# wisp-6-mcu.net
KiCad netlist of a schematic drawn in Altium Designer
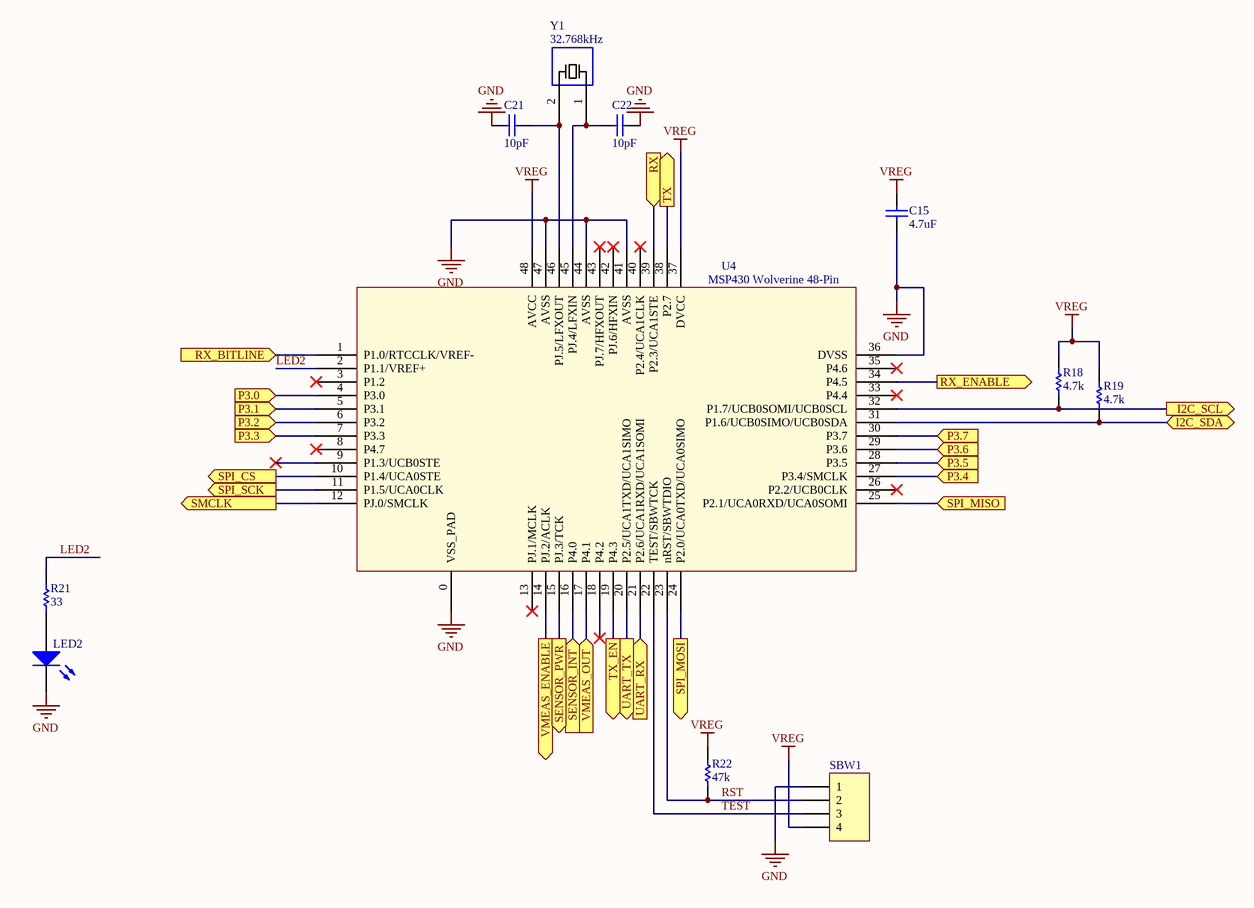
[diagram p0: wisp-6-mcu.SchDoc]

(export (version "E")
  (design (tool "Eeschema 10.0.6"))
  (components
    (comp (ref "C15")
      (value "4.7uF")
      (footprint "0402")
      (description "Ceramic Capacitor (Surface Mount)")
      (fields (field (name "MANUFACTURER") "Generic Ceramic Chip Cap (TBD)") (field (name "Comment") "Cap"))
      (libsource (lib "WISP_AD10") (part "Cap"))
    )
    (comp (ref "C21")
      (value "10pF")
      (footprint "0402")
      (description "Ceramic Capacitor (Surface Mount)")
      (fields (field (name "MANUFACTURER") "Generic Ceramic Chip Cap (TBD)") (field (name "Comment") "Cap"))
      (libsource (lib "WISP_AD10") (part "Cap"))
    )
    (comp (ref "C22")
      (value "10pF")
      (footprint "0402")
      (description "Ceramic Capacitor (Surface Mount)")
      (fields (field (name "MANUFACTURER") "Generic Ceramic Chip Cap (TBD)") (field (name "Comment") "Cap"))
      (libsource (lib "WISP_AD10") (part "Cap"))
    )
    (comp (ref "LED2")
      (value "LED")
      (footprint "Diode - 0603")
      (description "Typical RED, GREEN, YELLOW, AMBER GaAs LED")
      (libsource (lib "WISP_AD10") (part "Diode - LED"))
    )
    (comp (ref "R18")
      (value "4.7k")
      (footprint "0402")
      (description "Chip Resistor (Surface Mount)")
      (fields (field (name "MANUFACTURER") "Generic Chip Res (TBD)") (field (name "Comment") "Res"))
      (libsource (lib "WISP_AD10") (part "Res"))
    )
    (comp (ref "R19")
      (value "4.7k")
      (footprint "0402")
      (description "Chip Resistor (Surface Mount)")
      (fields (field (name "MANUFACTURER") "Generic Chip Res (TBD)") (field (name "Comment") "Res"))
      (libsource (lib "WISP_AD10") (part "Res"))
    )
    (comp (ref "R21")
      (value "33")
      (footprint "0402")
      (description "Chip Resistor (Surface Mount)")
      (fields (field (name "MANUFACTURER") "Generic Chip Res (TBD)") (field (name "Comment") "Res"))
      (libsource (lib "WISP_AD10") (part "Res"))
    )
    (comp (ref "R22")
      (value "47k")
      (footprint "0402")
      (description "Chip Resistor (Surface Mount)")
      (fields (field (name "MANUFACTURER") "Generic Chip Res (TBD)") (field (name "Comment") "Res"))
      (libsource (lib "WISP_AD10") (part "Res"))
    )
    (comp (ref "SBW1")
      (value "MHDR1X4")
      (footprint "MHDR1X4")
      (description "Header, 4-Pin")
      (fields (field (name "PUBLISHER") "Altium Limited"))
      (libsource (lib "Miscellaneous Connectors") (part "MHDR1X4"))
    )
    (comp (ref "U4")
      (value "MSP430 Wolverine 48-Pin")
      (footprint "MSP_QFN48_RGZ_PAD0")
      (description "16-bit FRAM MCU")
      (fields (field (name "PARTNUMBER") "MSP430FR5969"))
      (libsource (lib "WISP_AD10") (part "MSP430FR596X_586X_RGZ"))
    )
    (comp (ref "Y1")
      (value "32.768kHz")
      (footprint "XTAL [3.20mm x 1.50mm]")
      (description "Crystal Oscillator - [3.20mm x 1.50mm]")
      (fields
        (field (name "DIGI-KEY PART NUMBER") "example: SE2413CT-ND")
        (field (name "MANUFACTURER") "Epson Toyocom Corporation")
      )
      (libsource (lib "WISP_AD10") (part "XTAL 2-pins"))
    )
  )
  (nets
    (net (code "1") (name "/I2C_SCL") (class "Default")
      (node (ref "R18") (pin "1") (pinfunction "1_1") (pintype "passive"))
      (node (ref "U4") (pin "32") (pinfunction "P1.7/UCB0SOMI/UCB0SCL_32") (pintype "passive"))
    )
    (net (code "2") (name "/I2C_SDA") (class "Default")
      (node (ref "R19") (pin "1") (pinfunction "1_1") (pintype "passive"))
      (node (ref "U4") (pin "31") (pinfunction "P1.6/UCB0SIMO/UCB0SDA_31") (pintype "passive"))
    )
    (net (code "3") (name "/LED2") (class "Default")
      (node (ref "R21") (pin "2") (pinfunction "2_2") (pintype "passive"))
      (node (ref "U4") (pin "2") (pinfunction "P1.1/VREF+_2") (pintype "passive"))
    )
    (net (code "4") (name "/P3.0") (class "Default")
      (node (ref "U4") (pin "4") (pinfunction "P3.0_4") (pintype "passive"))
    )
    (net (code "5") (name "/P3.1") (class "Default")
      (node (ref "U4") (pin "5") (pinfunction "P3.1_5") (pintype "passive"))
    )
    (net (code "6") (name "/P3.2") (class "Default")
      (node (ref "U4") (pin "6") (pinfunction "P3.2_6") (pintype "passive"))
    )
    (net (code "7") (name "/P3.3") (class "Default")
      (node (ref "U4") (pin "7") (pinfunction "P3.3_7") (pintype "passive"))
    )
    (net (code "8") (name "/P3.4") (class "Default")
      (node (ref "U4") (pin "27") (pinfunction "P3.4/SMCLK_27") (pintype "passive"))
    )
    (net (code "9") (name "/P3.5") (class "Default")
      (node (ref "U4") (pin "28") (pinfunction "P3.5_28") (pintype "passive"))
    )
    (net (code "10") (name "/P3.6") (class "Default")
      (node (ref "U4") (pin "29") (pinfunction "P3.6_29") (pintype "passive"))
    )
    (net (code "11") (name "/P3.7") (class "Default")
      (node (ref "U4") (pin "30") (pinfunction "P3.7_30") (pintype "passive"))
    )
    (net (code "12") (name "/RST") (class "Default")
      (node (ref "R22") (pin "1") (pinfunction "1_1") (pintype "passive"))
      (node (ref "SBW1") (pin "2") (pinfunction "2_2") (pintype "passive"))
      (node (ref "U4") (pin "23") (pinfunction "nRST/SBWTDIO_23") (pintype "passive"))
    )
    (net (code "13") (name "/RX") (class "Default")
      (node (ref "U4") (pin "39") (pinfunction "P2.3/UCA1STE_39") (pintype "passive"))
    )
    (net (code "14") (name "/RX_BITLINE") (class "Default")
      (node (ref "U4") (pin "1") (pinfunction "P1.0/RTCCLK/VREF-_1") (pintype "passive"))
    )
    (net (code "15") (name "/RX_ENABLE") (class "Default")
      (node (ref "U4") (pin "34") (pinfunction "P4.5_34") (pintype "passive"))
    )
    (net (code "16") (name "/SENSOR_INT") (class "Default")
      (node (ref "U4") (pin "16") (pinfunction "P4.0_16") (pintype "passive"))
    )
    (net (code "17") (name "/SENSOR_PWR") (class "Default")
      (node (ref "U4") (pin "15") (pinfunction "PJ.3/TCK_15") (pintype "passive"))
    )
    (net (code "18") (name "/SMCLK") (class "Default")
      (node (ref "U4") (pin "12") (pinfunction "PJ.0/SMCLK_12") (pintype "passive"))
    )
    (net (code "19") (name "/SPI_CS") (class "Default")
      (node (ref "U4") (pin "10") (pinfunction "P1.4/UCA0STE_10") (pintype "passive"))
    )
    (net (code "20") (name "/SPI_MISO") (class "Default")
      (node (ref "U4") (pin "25") (pinfunction "P2.1/UCA0RXD/UCA0SOMI_25") (pintype "passive"))
    )
    (net (code "21") (name "/SPI_MOSI") (class "Default")
      (node (ref "U4") (pin "24") (pinfunction "P2.0/UCA0TXD/UCA0SIMO_24") (pintype "passive"))
    )
    (net (code "22") (name "/SPI_SCK") (class "Default")
      (node (ref "U4") (pin "11") (pinfunction "P1.5/UCA0CLK_11") (pintype "passive"))
    )
    (net (code "23") (name "/TEST") (class "Default")
      (node (ref "SBW1") (pin "3") (pinfunction "3_3") (pintype "passive"))
      (node (ref "U4") (pin "22") (pinfunction "TEST/SBWTCK_22") (pintype "passive"))
    )
    (net (code "24") (name "/TX") (class "Default")
      (node (ref "U4") (pin "38") (pinfunction "P2.7_38") (pintype "passive"))
    )
    (net (code "25") (name "/TX_EN") (class "Default")
      (node (ref "U4") (pin "19") (pinfunction "P4.3_19") (pintype "passive"))
    )
    (net (code "26") (name "/UART_RX") (class "Default")
      (node (ref "U4") (pin "21") (pinfunction "P2.6/UCA1RXD/UCA1SOMI_21") (pintype "passive"))
    )
    (net (code "27") (name "/UART_TX") (class "Default")
      (node (ref "U4") (pin "20") (pinfunction "P2.5/UCA1TXD/UCA1SIMO_20") (pintype "passive"))
    )
    (net (code "28") (name "/VMEAS_ENABLE") (class "Default")
      (node (ref "U4") (pin "14") (pinfunction "PJ.2/ACLK_14") (pintype "passive"))
    )
    (net (code "29") (name "/VMEAS_OUT") (class "Default")
      (node (ref "U4") (pin "17") (pinfunction "P4.1_17") (pintype "passive"))
    )
    (net (code "30") (name "GND") (class "Default")
      (node (ref "C15") (pin "1") (pinfunction "1_1") (pintype "passive"))
      (node (ref "C21") (pin "1") (pinfunction "1_1") (pintype "passive"))
      (node (ref "C22") (pin "1") (pinfunction "1_1") (pintype "passive"))
      (node (ref "LED2") (pin "2") (pinfunction "K_2") (pintype "passive"))
      (node (ref "SBW1") (pin "1") (pinfunction "1_1") (pintype "passive"))
      (node (ref "U4") (pin "0") (pinfunction "VSS_PAD_0") (pintype "passive"))
      (node (ref "U4") (pin "36") (pinfunction "DVSS_36") (pintype "passive"))
      (node (ref "U4") (pin "41") (pinfunction "AVSS_41") (pintype "passive"))
      (node (ref "U4") (pin "44") (pinfunction "AVSS_44") (pintype "passive"))
      (node (ref "U4") (pin "47") (pinfunction "AVSS_47") (pintype "passive"))
    )
    (net (code "31") (name "Net-(LED2-A)") (class "Default")
      (node (ref "LED2") (pin "1") (pinfunction "A_1") (pintype "passive"))
      (node (ref "R21") (pin "1") (pinfunction "1_1") (pintype "passive"))
    )
    (net (code "32") (name "Net-(U4-PJ.4{slash}LFXIN)") (class "Default")
      (node (ref "C22") (pin "2") (pinfunction "2_2") (pintype "passive"))
      (node (ref "U4") (pin "45") (pinfunction "PJ.4/LFXIN_45") (pintype "passive"))
      (node (ref "Y1") (pin "1") (pinfunction "1_1") (pintype "power_in"))
    )
    (net (code "33") (name "Net-(U4-PJ.5{slash}LFXOUT)") (class "Default")
      (node (ref "C21") (pin "2") (pinfunction "2_2") (pintype "passive"))
      (node (ref "U4") (pin "46") (pinfunction "PJ.5/LFXOUT_46") (pintype "passive"))
      (node (ref "Y1") (pin "2") (pinfunction "2_2") (pintype "power_in"))
    )
    (net (code "34") (name "VREG") (class "Default")
      (node (ref "C15") (pin "2") (pinfunction "2_2") (pintype "passive"))
      (node (ref "R18") (pin "2") (pinfunction "2_2") (pintype "passive"))
      (node (ref "R19") (pin "2") (pinfunction "2_2") (pintype "passive"))
      (node (ref "R22") (pin "2") (pinfunction "2_2") (pintype "passive"))
      (node (ref "SBW1") (pin "4") (pinfunction "4_4") (pintype "passive"))
      (node (ref "U4") (pin "37") (pinfunction "DVCC_37") (pintype "passive"))
      (node (ref "U4") (pin "48") (pinfunction "AVCC_48") (pintype "passive"))
    )
    (net (code "35") (name "unconnected-(U4-P1.2-Pad3)") (class "Default")
      (node (ref "U4") (pin "3") (pinfunction "P1.2_3") (pintype "passive+no_connect"))
    )
    (net (code "36") (name "unconnected-(U4-P1.3{slash}UCB0STE-Pad9)") (class "Default")
      (node (ref "U4") (pin "9") (pinfunction "P1.3/UCB0STE_9") (pintype "passive+no_connect"))
    )
    (net (code "37") (name "unconnected-(U4-P2.2{slash}UCB0CLK-Pad26)") (class "Default")
      (node (ref "U4") (pin "26") (pinfunction "P2.2/UCB0CLK_26") (pintype "passive+no_connect"))
    )
    (net (code "38") (name "unconnected-(U4-P2.4{slash}UCA1CLK-Pad40)") (class "Default")
      (node (ref "U4") (pin "40") (pinfunction "P2.4/UCA1CLK_40") (pintype "passive+no_connect"))
    )
    (net (code "39") (name "unconnected-(U4-P4.2-Pad18)") (class "Default")
      (node (ref "U4") (pin "18") (pinfunction "P4.2_18") (pintype "passive+no_connect"))
    )
    (net (code "40") (name "unconnected-(U4-P4.4-Pad33)") (class "Default")
      (node (ref "U4") (pin "33") (pinfunction "P4.4_33") (pintype "passive+no_connect"))
    )
    (net (code "41") (name "unconnected-(U4-P4.6-Pad35)") (class "Default")
      (node (ref "U4") (pin "35") (pinfunction "P4.6_35") (pintype "passive+no_connect"))
    )
    (net (code "42") (name "unconnected-(U4-P4.7-Pad8)") (class "Default")
      (node (ref "U4") (pin "8") (pinfunction "P4.7_8") (pintype "passive+no_connect"))
    )
    (net (code "43") (name "unconnected-(U4-PJ.1{slash}MCLK-Pad13)") (class "Default")
      (node (ref "U4") (pin "13") (pinfunction "PJ.1/MCLK_13") (pintype "passive+no_connect"))
    )
    (net (code "44") (name "unconnected-(U4-PJ.6{slash}HFXIN-Pad42)") (class "Default")
      (node (ref "U4") (pin "42") (pinfunction "PJ.6/HFXIN_42") (pintype "passive+no_connect"))
    )
    (net (code "45") (name "unconnected-(U4-PJ.7{slash}HFXOUT-Pad43)") (class "Default")
      (node (ref "U4") (pin "43") (pinfunction "PJ.7/HFXOUT_43") (pintype "passive+no_connect"))
    )
  )
)
